# octapentaveega_v2.net
KiCad netlist of a schematic drawn in EAGLE
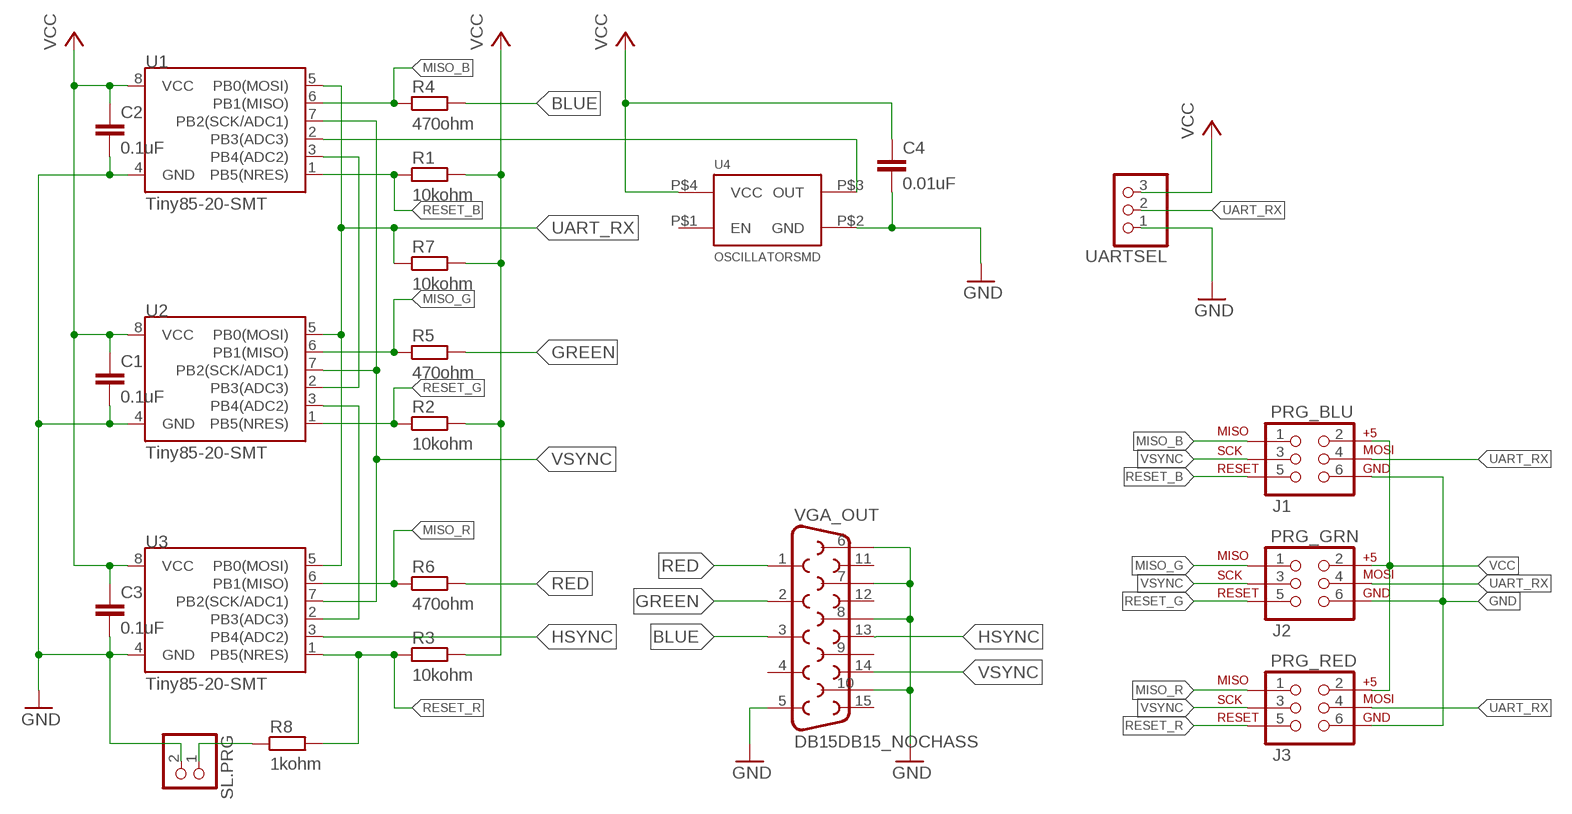
[diagram p0: schematic, sheet 1]

(export (version "E")
  (design (tool "Eeschema 10.0.6"))
  (components
    (comp (ref "C1")
      (value "0.1uF")
      (footprint "eagle-import:C0603")
      (libsource (lib "eagle-import") (part "CAPACITOR"))
    )
    (comp (ref "C2")
      (value "0.1uF")
      (footprint "eagle-import:C0603")
      (libsource (lib "eagle-import") (part "CAPACITOR"))
    )
    (comp (ref "C3")
      (value "0.1uF")
      (footprint "eagle-import:C0603")
      (libsource (lib "eagle-import") (part "CAPACITOR"))
    )
    (comp (ref "C4")
      (value "0.01uF")
      (footprint "eagle-import:C0603")
      (libsource (lib "eagle-import") (part "CAPACITOR"))
    )
    (comp (ref "PRG_BLU")
      (value "J1")
      (footprint "eagle-import:AVX_9188_6-WAY_MATING_GUIDE")
      (libsource (lib "eagle-import") (part "ISPTOUCH_HEADER"))
    )
    (comp (ref "PRG_GRN")
      (value "J2")
      (footprint "eagle-import:AVX_9188_6-WAY_MATING_GUIDE")
      (libsource (lib "eagle-import") (part "ISPTOUCH_HEADER"))
    )
    (comp (ref "PRG_RED")
      (value "J3")
      (footprint "eagle-import:AVX_9188_6-WAY_MATING_GUIDE")
      (libsource (lib "eagle-import") (part "ISPTOUCH_HEADER"))
    )
    (comp (ref "R1")
      (value "10kohm")
      (footprint "eagle-import:R0603")
      (libsource (lib "eagle-import") (part "RESISTOR"))
    )
    (comp (ref "R2")
      (value "10kohm")
      (footprint "eagle-import:R0603")
      (libsource (lib "eagle-import") (part "RESISTOR"))
    )
    (comp (ref "R3")
      (value "10kohm")
      (footprint "eagle-import:R0603")
      (libsource (lib "eagle-import") (part "RESISTOR"))
    )
    (comp (ref "R4")
      (value "470ohm")
      (footprint "eagle-import:R0603")
      (libsource (lib "eagle-import") (part "RESISTOR"))
    )
    (comp (ref "R5")
      (value "470ohm")
      (footprint "eagle-import:R0603")
      (libsource (lib "eagle-import") (part "RESISTOR"))
    )
    (comp (ref "R6")
      (value "470ohm")
      (footprint "eagle-import:R0603")
      (libsource (lib "eagle-import") (part "RESISTOR"))
    )
    (comp (ref "R7")
      (value "10kohm")
      (footprint "eagle-import:R0603")
      (libsource (lib "eagle-import") (part "RESISTOR"))
    )
    (comp (ref "R8")
      (value "1kohm")
      (footprint "eagle-import:R0603")
      (libsource (lib "eagle-import") (part "RESISTOR"))
    )
    (comp (ref "SL.PRG")
      (value "PINHD-1X02_2.54-S")
      (footprint "eagle-import:1X02-S")
      (libsource (lib "eagle-import") (part "PINHD-1X02_2.54-S"))
    )
    (comp (ref "U1")
      (value "Tiny85-20-SMT")
      (footprint "eagle-import:SO08-EIAJ")
      (libsource (lib "eagle-import") (part "ATTINY45TINY85-20-SMT"))
    )
    (comp (ref "U2")
      (value "Tiny85-20-SMT")
      (footprint "eagle-import:SO08-EIAJ")
      (libsource (lib "eagle-import") (part "ATTINY45TINY85-20-SMT"))
    )
    (comp (ref "U3")
      (value "Tiny85-20-SMT")
      (footprint "eagle-import:SO08-EIAJ")
      (libsource (lib "eagle-import") (part "ATTINY45TINY85-20-SMT"))
    )
    (comp (ref "U4")
      (value "OSCILLATORSMD")
      (footprint "eagle-import:CRYSTAL-SMD-7X5")
      (libsource (lib "eagle-import") (part "OSCILLATORSMD"))
    )
    (comp (ref "UARTSEL")
      (value "PINHD-1X03_2.54-S")
      (footprint "eagle-import:1X03-S")
      (libsource (lib "eagle-import") (part "PINHD-1X03_2.54-S"))
    )
    (comp (ref "VGA_OUT")
      (value "DB15DB15_NOCHASS")
      (footprint "eagle-import:DB15_NOCHASS")
      (libsource (lib "eagle-import") (part "DB15DB15_NOCHASS"))
    )
  )
  (nets
    (net (code "1") (name "BLUE") (class "Default")
      (node (ref "R4") (pin "2") (pinfunction "2_2") (pintype "passive"))
      (node (ref "VGA_OUT") (pin "3") (pinfunction "3_3") (pintype "passive"))
    )
    (net (code "2") (name "GND") (class "Default")
      (node (ref "C1") (pin "2") (pinfunction "2_2") (pintype "passive"))
      (node (ref "C2") (pin "2") (pinfunction "2_2") (pintype "passive"))
      (node (ref "C3") (pin "2") (pinfunction "2_2") (pintype "passive"))
      (node (ref "C4") (pin "2") (pinfunction "2_2") (pintype "passive"))
      (node (ref "PRG_BLU") (pin "6") (pinfunction "6_6") (pintype "passive"))
      (node (ref "PRG_GRN") (pin "6") (pinfunction "6_6") (pintype "passive"))
      (node (ref "PRG_RED") (pin "6") (pinfunction "6_6") (pintype "passive"))
      (node (ref "SL.PRG") (pin "2") (pinfunction "2_2") (pintype "passive"))
      (node (ref "U1") (pin "4") (pinfunction "GND_4") (pintype "bidirectional"))
      (node (ref "U2") (pin "4") (pinfunction "GND_4") (pintype "bidirectional"))
      (node (ref "U3") (pin "4") (pinfunction "GND_4") (pintype "bidirectional"))
      (node (ref "U4") (pin "P$2") (pinfunction "GND_P$2") (pintype "bidirectional"))
      (node (ref "UARTSEL") (pin "1") (pinfunction "1_1") (pintype "passive"))
      (node (ref "VGA_OUT") (pin "10") (pinfunction "10_10") (pintype "passive"))
      (node (ref "VGA_OUT") (pin "5") (pinfunction "5_5") (pintype "passive"))
      (node (ref "VGA_OUT") (pin "6") (pinfunction "6_6") (pintype "passive"))
      (node (ref "VGA_OUT") (pin "7") (pinfunction "7_7") (pintype "passive"))
      (node (ref "VGA_OUT") (pin "8") (pinfunction "8_8") (pintype "passive"))
    )
    (net (code "3") (name "GREEN") (class "Default")
      (node (ref "R5") (pin "2") (pinfunction "2_2") (pintype "passive"))
      (node (ref "VGA_OUT") (pin "2") (pinfunction "2_2") (pintype "passive"))
    )
    (net (code "4") (name "HSYNC") (class "Default")
      (node (ref "U3") (pin "3") (pinfunction "PB4(ADC2)_3") (pintype "bidirectional"))
      (node (ref "VGA_OUT") (pin "13") (pinfunction "13_13") (pintype "passive"))
    )
    (net (code "5") (name "MISO_B") (class "Default")
      (node (ref "PRG_BLU") (pin "1") (pinfunction "1_1") (pintype "passive"))
      (node (ref "R4") (pin "1") (pinfunction "1_1") (pintype "passive"))
      (node (ref "U1") (pin "6") (pinfunction "PB1(MISO)_6") (pintype "bidirectional"))
    )
    (net (code "6") (name "MISO_G") (class "Default")
      (node (ref "PRG_GRN") (pin "1") (pinfunction "1_1") (pintype "passive"))
      (node (ref "R5") (pin "1") (pinfunction "1_1") (pintype "passive"))
      (node (ref "U2") (pin "6") (pinfunction "PB1(MISO)_6") (pintype "bidirectional"))
    )
    (net (code "7") (name "MISO_R") (class "Default")
      (node (ref "PRG_RED") (pin "1") (pinfunction "1_1") (pintype "passive"))
      (node (ref "R6") (pin "1") (pinfunction "1_1") (pintype "passive"))
      (node (ref "U3") (pin "6") (pinfunction "PB1(MISO)_6") (pintype "bidirectional"))
    )
    (net (code "8") (name "Net-(R8-Pad1)") (class "Default")
      (node (ref "R8") (pin "1") (pinfunction "1_1") (pintype "passive"))
      (node (ref "SL.PRG") (pin "1") (pinfunction "1_1") (pintype "passive"))
    )
    (net (code "9") (name "Net-(U1-PB3(ADC3))") (class "Default")
      (node (ref "U1") (pin "2") (pinfunction "PB3(ADC3)_2") (pintype "bidirectional"))
      (node (ref "U4") (pin "P$3") (pinfunction "OUT_P$3") (pintype "bidirectional"))
    )
    (net (code "10") (name "Net-(U1-PB4(ADC2))") (class "Default")
      (node (ref "U1") (pin "3") (pinfunction "PB4(ADC2)_3") (pintype "bidirectional"))
      (node (ref "U2") (pin "2") (pinfunction "PB3(ADC3)_2") (pintype "bidirectional"))
    )
    (net (code "11") (name "Net-(U2-PB4(ADC2))") (class "Default")
      (node (ref "U2") (pin "3") (pinfunction "PB4(ADC2)_3") (pintype "bidirectional"))
      (node (ref "U3") (pin "2") (pinfunction "PB3(ADC3)_2") (pintype "bidirectional"))
    )
    (net (code "12") (name "RED") (class "Default")
      (node (ref "R6") (pin "2") (pinfunction "2_2") (pintype "passive"))
      (node (ref "VGA_OUT") (pin "1") (pinfunction "1_1") (pintype "passive"))
    )
    (net (code "13") (name "RESET_B") (class "Default")
      (node (ref "PRG_BLU") (pin "5") (pinfunction "5_5") (pintype "passive"))
      (node (ref "R1") (pin "1") (pinfunction "1_1") (pintype "passive"))
      (node (ref "U1") (pin "1") (pinfunction "PB5(NRES)_1") (pintype "bidirectional"))
    )
    (net (code "14") (name "RESET_G") (class "Default")
      (node (ref "PRG_GRN") (pin "5") (pinfunction "5_5") (pintype "passive"))
      (node (ref "R2") (pin "1") (pinfunction "1_1") (pintype "passive"))
      (node (ref "U2") (pin "1") (pinfunction "PB5(NRES)_1") (pintype "bidirectional"))
    )
    (net (code "15") (name "RESET_R") (class "Default")
      (node (ref "PRG_RED") (pin "5") (pinfunction "5_5") (pintype "passive"))
      (node (ref "R3") (pin "1") (pinfunction "1_1") (pintype "passive"))
      (node (ref "R8") (pin "2") (pinfunction "2_2") (pintype "passive"))
      (node (ref "U3") (pin "1") (pinfunction "PB5(NRES)_1") (pintype "bidirectional"))
    )
    (net (code "16") (name "UART_RX") (class "Default")
      (node (ref "PRG_BLU") (pin "4") (pinfunction "4_4") (pintype "passive"))
      (node (ref "PRG_GRN") (pin "4") (pinfunction "4_4") (pintype "passive"))
      (node (ref "PRG_RED") (pin "4") (pinfunction "4_4") (pintype "passive"))
      (node (ref "R7") (pin "1") (pinfunction "1_1") (pintype "passive"))
      (node (ref "U1") (pin "5") (pinfunction "PB0(MOSI)_5") (pintype "bidirectional"))
      (node (ref "U2") (pin "5") (pinfunction "PB0(MOSI)_5") (pintype "bidirectional"))
      (node (ref "U3") (pin "5") (pinfunction "PB0(MOSI)_5") (pintype "bidirectional"))
      (node (ref "UARTSEL") (pin "2") (pinfunction "2_2") (pintype "passive"))
    )
    (net (code "17") (name "VCC") (class "Default")
      (node (ref "C1") (pin "1") (pinfunction "1_1") (pintype "passive"))
      (node (ref "C2") (pin "1") (pinfunction "1_1") (pintype "passive"))
      (node (ref "C3") (pin "1") (pinfunction "1_1") (pintype "passive"))
      (node (ref "C4") (pin "1") (pinfunction "1_1") (pintype "passive"))
      (node (ref "PRG_BLU") (pin "2") (pinfunction "2_2") (pintype "passive"))
      (node (ref "PRG_GRN") (pin "2") (pinfunction "2_2") (pintype "passive"))
      (node (ref "PRG_RED") (pin "2") (pinfunction "2_2") (pintype "passive"))
      (node (ref "R1") (pin "2") (pinfunction "2_2") (pintype "passive"))
      (node (ref "R2") (pin "2") (pinfunction "2_2") (pintype "passive"))
      (node (ref "R3") (pin "2") (pinfunction "2_2") (pintype "passive"))
      (node (ref "R7") (pin "2") (pinfunction "2_2") (pintype "passive"))
      (node (ref "U1") (pin "8") (pinfunction "VCC_8") (pintype "bidirectional"))
      (node (ref "U2") (pin "8") (pinfunction "VCC_8") (pintype "bidirectional"))
      (node (ref "U3") (pin "8") (pinfunction "VCC_8") (pintype "bidirectional"))
      (node (ref "U4") (pin "P$4") (pinfunction "VCC_P$4") (pintype "bidirectional"))
      (node (ref "UARTSEL") (pin "3") (pinfunction "3_3") (pintype "passive"))
    )
    (net (code "18") (name "VSYNC") (class "Default")
      (node (ref "PRG_BLU") (pin "3") (pinfunction "3_3") (pintype "passive"))
      (node (ref "PRG_GRN") (pin "3") (pinfunction "3_3") (pintype "passive"))
      (node (ref "PRG_RED") (pin "3") (pinfunction "3_3") (pintype "passive"))
      (node (ref "U1") (pin "7") (pinfunction "PB2(SCK/ADC1)_7") (pintype "bidirectional"))
      (node (ref "U2") (pin "7") (pinfunction "PB2(SCK/ADC1)_7") (pintype "bidirectional"))
      (node (ref "U3") (pin "7") (pinfunction "PB2(SCK/ADC1)_7") (pintype "bidirectional"))
      (node (ref "VGA_OUT") (pin "14") (pinfunction "14_14") (pintype "passive"))
    )
    (net (code "19") (name "unconnected-(U4-EN-PadP$1)") (class "Default")
      (node (ref "U4") (pin "P$1") (pinfunction "EN_P$1") (pintype "bidirectional"))
    )
    (net (code "20") (name "unconnected-(VGA_OUT-Pad4)") (class "Default")
      (node (ref "VGA_OUT") (pin "4") (pinfunction "4_4") (pintype "passive"))
    )
    (net (code "21") (name "unconnected-(VGA_OUT-Pad9)") (class "Default")
      (node (ref "VGA_OUT") (pin "9") (pinfunction "9_9") (pintype "passive"))
    )
    (net (code "22") (name "unconnected-(VGA_OUT-Pad11)") (class "Default")
      (node (ref "VGA_OUT") (pin "11") (pinfunction "11_11") (pintype "passive"))
    )
    (net (code "23") (name "unconnected-(VGA_OUT-Pad12)") (class "Default")
      (node (ref "VGA_OUT") (pin "12") (pinfunction "12_12") (pintype "passive"))
    )
    (net (code "24") (name "unconnected-(VGA_OUT-Pad15)") (class "Default")
      (node (ref "VGA_OUT") (pin "15") (pinfunction "15_15") (pintype "passive"))
    )
  )
)
